# initial.net
KiCad netlist of a schematic drawn in Altium Designer
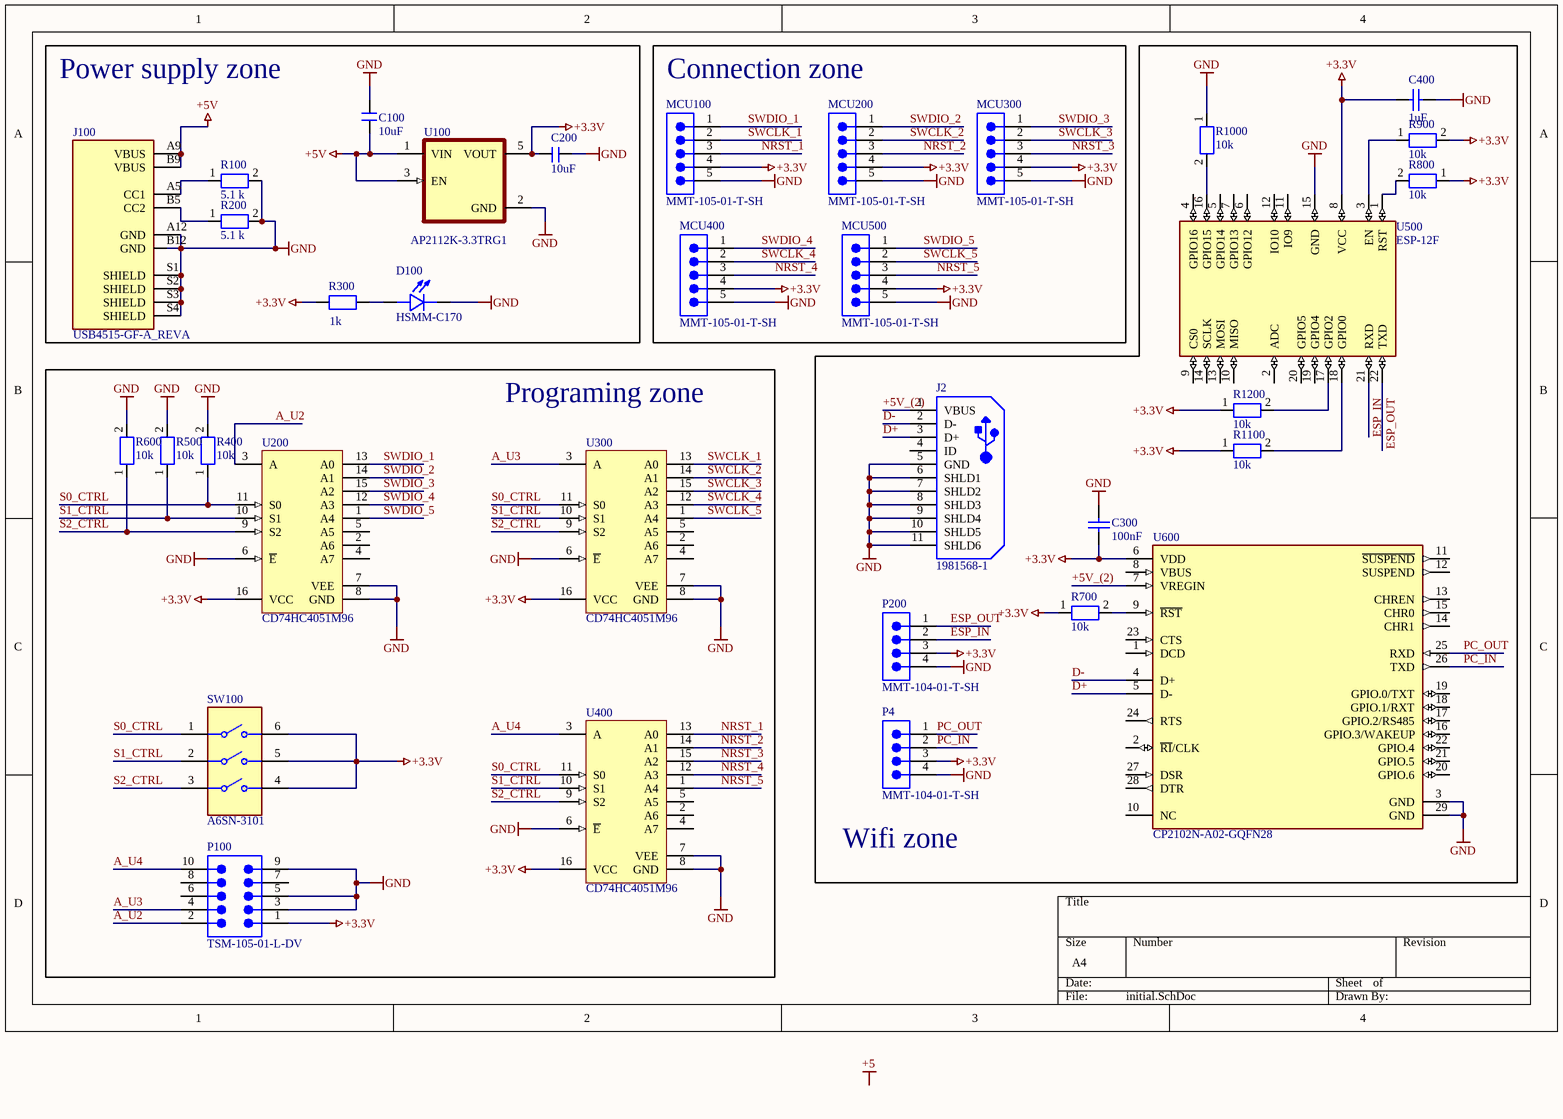
[diagram p0: initial.SchDoc]

(export (version "E")
  (design (tool "Eeschema 10.0.6"))
  (components
    (comp (ref "C100")
      (value "10uF")
      (footprint "CAPC2012X145N")
      (description "10 ÂµF Â±10% 25V Ceramic Capacitor X5R 0805 (2012 Metric)")
      (fields (field (name "MF") "Samsung") (field (name "MP") "CL21A106KAYNNNE"))
      (libsource (lib "CL21A106KAYNNNE") (part "CL21A106KAYNNNE"))
    )
    (comp (ref "C200")
      (value "10uF")
      (footprint "CAPC2012X145N")
      (description "10 ÂµF Â±10% 25V Ceramic Capacitor X5R 0805 (2012 Metric)")
      (fields (field (name "MF") "Samsung") (field (name "MP") "CL21A106KAYNNNE"))
      (libsource (lib "CL21A106KAYNNNE") (part "CL21A106KAYNNNE"))
    )
    (comp (ref "C300")
      (value "100nF")
      (footprint "CAPC2013X135X50LL15T20")
      (fields (field (name "MANUFACTURER") "Vitramon") (field (name "PART NUMBER") "VJ0805Y104KXJCW1BC"))
      (libsource (lib "Altium Content Vault") (part "CAP"))
    )
    (comp (ref "C400")
      (value "1uF")
      (footprint "CAPC2013X140X50NL20T25")
      (fields
        (field (name "PART NUMBER") "0805YD105MAT2A")
        (field (name "MANUFACTURER") "AVX Interconnect / Elco")
      )
      (libsource (lib "Altium Content Vault") (part "CAP"))
    )
    (comp (ref "D100")
      (value "HSMM-C170")
      (footprint "LED_HSMM-C170")
      (libsource (lib "HSMM-C170") (part "HSMM-C170"))
    )
    (comp (ref "J2")
      (value "1981568-1")
      (footprint "TECO-1981568-5_V")
      (description "Micro USB Receptacle Standard Type B Assy, 5-Pin SMD, RoHS, Tape and Reel")
      (fields (field (name "MANUFACTURER") "TE Connectivity"))
      (libsource (lib "Altium Content Vault") (part "USB-5-6SHLD"))
    )
    (comp (ref "J100")
      (value "USB4515-GF-A_REVA")
      (footprint "GCT_USB4515-GF-A_REVA")
      (description "Type C USB Charging Connector")
      (fields
        (field (name "MF") "Global Connector Technology")
        (field (name "DIGI-KEY_PART_NUMBER") "2073-USB4515-GF-ATR-ND")
      )
      (libsource (lib "USB4515-GF-A_REVA") (part "USB4515-GF-A_REVA"))
    )
    (comp (ref "MCU100")
      (value "MMT-105-01-T-SH")
      (footprint "SMTC-MMT-105-01-X-SH")
      (description "Horizontal Surface Mount Header, -55 to 105 degC, 2 mm Pitch, 5-Pin, Male, RoHS")
      (fields (field (name "MANUFACTURER") "Samtec"))
      (libsource (lib "Altium Content Vault") (part "SMTC-MMT-105-01-X-SH"))
    )
    (comp (ref "MCU200")
      (value "MMT-105-01-T-SH")
      (footprint "SMTC-MMT-105-01-X-SH")
      (description "Horizontal Surface Mount Header, -55 to 105 degC, 2 mm Pitch, 5-Pin, Male, RoHS")
      (fields (field (name "MANUFACTURER") "Samtec"))
      (libsource (lib "Altium Content Vault") (part "SMTC-MMT-105-01-X-SH"))
    )
    (comp (ref "MCU300")
      (value "MMT-105-01-T-SH")
      (footprint "SMTC-MMT-105-01-X-SH")
      (description "Horizontal Surface Mount Header, -55 to 105 degC, 2 mm Pitch, 5-Pin, Male, RoHS")
      (fields (field (name "MANUFACTURER") "Samtec"))
      (libsource (lib "Altium Content Vault") (part "SMTC-MMT-105-01-X-SH"))
    )
    (comp (ref "MCU400")
      (value "MMT-105-01-T-SH")
      (footprint "SMTC-MMT-105-01-X-SH")
      (description "Horizontal Surface Mount Header, -55 to 105 degC, 2 mm Pitch, 5-Pin, Male, RoHS")
      (fields (field (name "MANUFACTURER") "Samtec"))
      (libsource (lib "Altium Content Vault") (part "SMTC-MMT-105-01-X-SH"))
    )
    (comp (ref "MCU500")
      (value "MMT-105-01-T-SH")
      (footprint "SMTC-MMT-105-01-X-SH")
      (description "Horizontal Surface Mount Header, -55 to 105 degC, 2 mm Pitch, 5-Pin, Male, RoHS")
      (fields (field (name "MANUFACTURER") "Samtec"))
      (libsource (lib "Altium Content Vault") (part "SMTC-MMT-105-01-X-SH"))
    )
    (comp (ref "P4")
      (value "MMT-104-01-T-SH")
      (footprint "SMTC-MMT-104-01-X-SH")
      (description "Horizontal Surface Mount Header, -55 to 105 degC, 2 mm Pitch, 4-Pin, Male, RoHS")
      (fields (field (name "MANUFACTURER") "Samtec"))
      (libsource (lib "Altium Content Vault") (part "SMTC-MMT-104-X-X-SH"))
    )
    (comp (ref "P100")
      (value "TSM-105-01-L-DV")
      (footprint "SMTC-TSM-105-01-X-DV")
      (fields (field (name "MANUFACTURER") "Samtec"))
      (libsource (lib "Altium Content Vault") (part "SMTC-TSM-105-01-X-X"))
    )
    (comp (ref "P200")
      (value "MMT-104-01-T-SH")
      (footprint "SMTC-MMT-104-01-X-SH")
      (description "Horizontal Surface Mount Header, -55 to 105 degC, 2 mm Pitch, 4-Pin, Male, RoHS")
      (fields (field (name "MANUFACTURER") "Samtec"))
      (libsource (lib "Altium Content Vault") (part "SMTC-MMT-104-X-X-SH"))
    )
    (comp (ref "R100")
      (value "5.1 k")
      (footprint "FP-KTR10-IPC_B")
      (description "Res Thick Film 0805 5.1kΩ 1% 0.125W ±100ppm/°C Automotive Paper T/R")
      (fields (field (name "TOLERANCE") "1%"))
      (libsource (lib "Rez5.1") (part "CMP-08839-031572-1"))
    )
    (comp (ref "R200")
      (value "5.1 k")
      (footprint "FP-KTR10-IPC_B")
      (description "Res Thick Film 0805 5.1kΩ 1% 0.125W ±100ppm/°C Automotive Paper T/R")
      (fields (field (name "TOLERANCE") "1%"))
      (libsource (lib "Rez5.1") (part "CMP-08839-031572-1"))
    )
    (comp (ref "R300")
      (value "1k")
      (footprint "RESC2012X60N")
      (fields (field (name "MP") "CRS0805-JX-102ELF") (field (name "MF") "Bourns"))
      (libsource (lib "1Kohm_rez") (part "CRS0805-JX-102ELF"))
    )
    (comp (ref "R400")
      (value "10k")
      (footprint "FP-CRGP0805-IPC_A")
      (description "CRGP 0805 10K 1%")
      (fields (field (name "MANUFACTURER PART NUMBER") "CRGP0805F10K") (field (name "MANUFACTURER") "TE"))
      (libsource (lib "Rez_5.1K_0805") (part "CMP-03211-006861-1"))
    )
    (comp (ref "R500")
      (value "10k")
      (footprint "FP-CRGP0805-IPC_A")
      (description "CRGP 0805 10K 1%")
      (fields (field (name "MANUFACTURER PART NUMBER") "CRGP0805F10K") (field (name "MANUFACTURER") "TE"))
      (libsource (lib "Rez_5.1K_0805") (part "CMP-03211-006861-1"))
    )
    (comp (ref "R600")
      (value "10k")
      (footprint "FP-CRGP0805-IPC_A")
      (description "CRGP 0805 10K 1%")
      (fields (field (name "MANUFACTURER PART NUMBER") "CRGP0805F10K") (field (name "MANUFACTURER") "TE"))
      (libsource (lib "Rez_5.1K_0805") (part "CMP-03211-006861-1"))
    )
    (comp (ref "R700")
      (value "10k")
      (footprint "FP-CRGP0805-IPC_A")
      (description "CRGP 0805 10K 1%")
      (fields (field (name "MANUFACTURER PART NUMBER") "CRGP0805F10K") (field (name "MANUFACTURER") "TE"))
      (libsource (lib "Rez_5.1K_0805") (part "CMP-03211-006861-1"))
    )
    (comp (ref "R800")
      (value "10k")
      (footprint "FP-CRGP0805-IPC_A")
      (description "CRGP 0805 10K 1%")
      (fields (field (name "MANUFACTURER PART NUMBER") "CRGP0805F10K") (field (name "MANUFACTURER") "TE"))
      (libsource (lib "Rez_5.1K_0805") (part "CMP-03211-006861-1"))
    )
    (comp (ref "R900")
      (value "10k")
      (footprint "FP-CRGP0805-IPC_A")
      (description "CRGP 0805 10K 1%")
      (fields (field (name "MANUFACTURER PART NUMBER") "CRGP0805F10K") (field (name "MANUFACTURER") "TE"))
      (libsource (lib "Rez_5.1K_0805") (part "CMP-03211-006861-1"))
    )
    (comp (ref "R1000")
      (value "10k")
      (footprint "FP-CRGP0805-IPC_A")
      (description "CRGP 0805 10K 1%")
      (fields (field (name "MANUFACTURER PART NUMBER") "CRGP0805F10K") (field (name "MANUFACTURER") "TE"))
      (libsource (lib "Rez_5.1K_0805") (part "CMP-03211-006861-1"))
    )
    (comp (ref "R1100")
      (value "10k")
      (footprint "FP-CRGP0805-IPC_A")
      (description "CRGP 0805 10K 1%")
      (fields (field (name "MANUFACTURER PART NUMBER") "CRGP0805F10K") (field (name "MANUFACTURER") "TE"))
      (libsource (lib "Rez_5.1K_0805") (part "CMP-03211-006861-1"))
    )
    (comp (ref "R1200")
      (value "10k")
      (footprint "FP-CRGP0805-IPC_A")
      (description "CRGP 0805 10K 1%")
      (fields (field (name "MANUFACTURER PART NUMBER") "CRGP0805F10K") (field (name "MANUFACTURER") "TE"))
      (libsource (lib "Rez_5.1K_0805") (part "CMP-03211-006861-1"))
    )
    (comp (ref "SW100")
      (value "A6SN-3101")
      (footprint "FP-A6SN-3101-MFG")
      (description "SWITCH SLIDE DIP SPST 25MA 24V")
      (fields
        (field (name "MANUFACTURER") "Omron Electronics Inc-EMC Div")
        (field (name "OCTOPART") "https://octopart.com/a6sn-3101-omron-55396000")
      )
      (libsource (lib "Altium Content Vault") (part "c5ed29025a0a80be921a75429a93ff4"))
    )
    (comp (ref "U100")
      (value "AP2112K-3.3TRG1")
      (footprint "SOT95P285X140-5N")
      (description "Linear Voltage Regulator IC Positive Fixed 1 Output 600mA SOT-25")
      (fields (field (name "MF") "Diodes Inc."))
      (libsource (lib "AP2112K-3.3TRG1") (part "AP2112K-3.3TRG1"))
    )
    (comp (ref "U200")
      (value "CD74HC4051M96")
      (footprint "D0016A_M")
      (description "High Speed CMOS 8-Channel Analog Multiplexer/Demultiplexer, D0016A, LARGE T&R")
      (fields
        (field (name "GENERIC PART NUMBER") "CD74HC4051")
        (field (name "MANUFACTURER") "Texas Instruments")
      )
      (libsource (lib "Altium Content Vault") (part "TI-CD74HCX4051-16"))
    )
    (comp (ref "U300")
      (value "CD74HC4051M96")
      (footprint "D0016A_M")
      (description "High Speed CMOS 8-Channel Analog Multiplexer/Demultiplexer, D0016A, LARGE T&R")
      (fields
        (field (name "GENERIC PART NUMBER") "CD74HC4051")
        (field (name "MANUFACTURER") "Texas Instruments")
      )
      (libsource (lib "Altium Content Vault") (part "TI-CD74HCX4051-16"))
    )
    (comp (ref "U400")
      (value "CD74HC4051M96")
      (footprint "D0016A_M")
      (description "High Speed CMOS 8-Channel Analog Multiplexer/Demultiplexer, D0016A, LARGE T&R")
      (fields
        (field (name "GENERIC PART NUMBER") "CD74HC4051")
        (field (name "MANUFACTURER") "Texas Instruments")
      )
      (libsource (lib "Altium Content Vault") (part "TI-CD74HCX4051-16"))
    )
    (comp (ref "U500")
      (value "ESP-12F")
      (footprint "ESP-12F")
      (description "WiFi Module")
      (fields (field (name "MF") "AI-Thinker"))
      (libsource (lib "ESP-12F") (part "ESP-12F"))
    )
    (comp (ref "U600")
      (value "CP2102N-A02-GQFN28")
      (footprint "FP-CP2102N-A02-GQFN28-MFG")
      (description "IC USB TO UART BRIDGE QFN28")
      (libsource (lib "Altium Content Vault") (part "f8fb43f618a03b32512863a7a8093b6"))
    )
  )
  (nets
    (net (code "1") (name "+3.3V") (class "Default")
      (node (ref "C200") (pin "1") (pinfunction "1_1") (pintype "passive"))
      (node (ref "C300") (pin "1") (pinfunction "1_1") (pintype "passive"))
      (node (ref "C400") (pin "2") (pinfunction "2_2") (pintype "passive"))
      (node (ref "MCU100") (pin "4") (pinfunction "4_4") (pintype "passive"))
      (node (ref "MCU200") (pin "4") (pinfunction "4_4") (pintype "passive"))
      (node (ref "MCU300") (pin "4") (pinfunction "4_4") (pintype "passive"))
      (node (ref "MCU400") (pin "4") (pinfunction "4_4") (pintype "passive"))
      (node (ref "MCU500") (pin "4") (pinfunction "4_4") (pintype "passive"))
      (node (ref "P100") (pin "1") (pinfunction "1_1") (pintype "passive"))
      (node (ref "P200") (pin "3") (pinfunction "3_3") (pintype "passive"))
      (node (ref "P4") (pin "3") (pinfunction "3_3") (pintype "passive"))
      (node (ref "R1100") (pin "1") (pinfunction "1_1") (pintype "passive"))
      (node (ref "R1200") (pin "1") (pinfunction "1_1") (pintype "passive"))
      (node (ref "R300") (pin "1") (pinfunction "1_1") (pintype "passive"))
      (node (ref "R700") (pin "1") (pinfunction "1_1") (pintype "passive"))
      (node (ref "R800") (pin "1") (pinfunction "1_1") (pintype "passive"))
      (node (ref "R900") (pin "2") (pinfunction "2_2") (pintype "passive"))
      (node (ref "SW100") (pin "4") (pinfunction "4_4") (pintype "passive"))
      (node (ref "SW100") (pin "5") (pinfunction "5_5") (pintype "passive"))
      (node (ref "SW100") (pin "6") (pinfunction "6_6") (pintype "passive"))
      (node (ref "U100") (pin "5") (pinfunction "VOUT_5") (pintype "power_in"))
      (node (ref "U200") (pin "16") (pinfunction "VCC_16") (pintype "power_in"))
      (node (ref "U300") (pin "16") (pinfunction "VCC_16") (pintype "power_in"))
      (node (ref "U400") (pin "16") (pinfunction "VCC_16") (pintype "power_in"))
      (node (ref "U500") (pin "8") (pinfunction "VCC_8") (pintype "bidirectional"))
      (node (ref "U600") (pin "6") (pinfunction "VDD_6") (pintype "power_in"))
    )
    (net (code "3") (name "+5V") (class "Default")
      (node (ref "C100") (pin "2") (pinfunction "2_2") (pintype "passive"))
      (node (ref "J100") (pin "A9") (pinfunction "VBUS_A9") (pintype "power_in"))
      (node (ref "J100") (pin "B9") (pinfunction "VBUS_B9") (pintype "power_in"))
      (node (ref "U100") (pin "1") (pinfunction "VIN_1") (pintype "power_in"))
      (node (ref "U100") (pin "3") (pinfunction "EN_3") (pintype "input"))
    )
    (net (code "4") (name "/+5V_(2)") (class "Default")
      (node (ref "J2") (pin "1") (pinfunction "VBUS_1") (pintype "passive"))
      (node (ref "U600") (pin "7") (pinfunction "VREGIN_7") (pintype "input"))
    )
    (net (code "5") (name "/A_U2") (class "Default")
      (node (ref "P100") (pin "2") (pinfunction "2_2") (pintype "passive"))
      (node (ref "U200") (pin "3") (pinfunction "A_3") (pintype "passive"))
    )
    (net (code "6") (name "/A_U3") (class "Default")
      (node (ref "P100") (pin "4") (pinfunction "4_4") (pintype "passive"))
      (node (ref "U300") (pin "3") (pinfunction "A_3") (pintype "passive"))
    )
    (net (code "7") (name "/A_U4") (class "Default")
      (node (ref "P100") (pin "10") (pinfunction "10_10") (pintype "passive"))
      (node (ref "U400") (pin "3") (pinfunction "A_3") (pintype "passive"))
    )
    (net (code "8") (name "/D+") (class "Default")
      (node (ref "J2") (pin "3") (pinfunction "D+_3") (pintype "passive"))
      (node (ref "U600") (pin "5") (pinfunction "D-_5") (pintype "passive"))
    )
    (net (code "9") (name "/D-") (class "Default")
      (node (ref "J2") (pin "2") (pinfunction "D-_2") (pintype "passive"))
      (node (ref "U600") (pin "4") (pinfunction "D+_4") (pintype "passive"))
    )
    (net (code "10") (name "/ESP_IN") (class "Default")
      (node (ref "P200") (pin "2") (pinfunction "2_2") (pintype "passive"))
      (node (ref "U500") (pin "21") (pinfunction "RXD_21") (pintype "bidirectional"))
    )
    (net (code "11") (name "/ESP_OUT") (class "Default")
      (node (ref "P200") (pin "1") (pinfunction "1_1") (pintype "passive"))
      (node (ref "U500") (pin "22") (pinfunction "TXD_22") (pintype "bidirectional"))
    )
    (net (code "12") (name "/NRST_1") (class "Default")
      (node (ref "MCU100") (pin "3") (pinfunction "3_3") (pintype "passive"))
      (node (ref "U400") (pin "13") (pinfunction "A0_13") (pintype "passive"))
    )
    (net (code "13") (name "/NRST_2") (class "Default")
      (node (ref "MCU200") (pin "3") (pinfunction "3_3") (pintype "passive"))
      (node (ref "U400") (pin "14") (pinfunction "A1_14") (pintype "passive"))
    )
    (net (code "14") (name "/NRST_3") (class "Default")
      (node (ref "MCU300") (pin "3") (pinfunction "3_3") (pintype "passive"))
      (node (ref "U400") (pin "15") (pinfunction "A2_15") (pintype "passive"))
    )
    (net (code "15") (name "/NRST_4") (class "Default")
      (node (ref "MCU400") (pin "3") (pinfunction "3_3") (pintype "passive"))
      (node (ref "U400") (pin "12") (pinfunction "A3_12") (pintype "passive"))
    )
    (net (code "16") (name "/NRST_5") (class "Default")
      (node (ref "MCU500") (pin "3") (pinfunction "3_3") (pintype "passive"))
      (node (ref "U400") (pin "1") (pinfunction "A4_1") (pintype "passive"))
    )
    (net (code "17") (name "/PC_IN") (class "Default")
      (node (ref "P4") (pin "2") (pinfunction "2_2") (pintype "passive"))
      (node (ref "U600") (pin "26") (pinfunction "TXD_26") (pintype "output"))
    )
    (net (code "18") (name "/PC_OUT") (class "Default")
      (node (ref "P4") (pin "1") (pinfunction "1_1") (pintype "passive"))
      (node (ref "U600") (pin "25") (pinfunction "RXD_25") (pintype "input"))
    )
    (net (code "19") (name "/S0_CTRL") (class "Default")
      (node (ref "R400") (pin "1") (pinfunction "1_1") (pintype "passive"))
      (node (ref "SW100") (pin "1") (pinfunction "1_1") (pintype "passive"))
      (node (ref "U200") (pin "11") (pinfunction "S0_11") (pintype "input"))
      (node (ref "U300") (pin "11") (pinfunction "S0_11") (pintype "input"))
      (node (ref "U400") (pin "11") (pinfunction "S0_11") (pintype "input"))
    )
    (net (code "20") (name "/S1_CTRL") (class "Default")
      (node (ref "R500") (pin "1") (pinfunction "1_1") (pintype "passive"))
      (node (ref "SW100") (pin "2") (pinfunction "2_2") (pintype "passive"))
      (node (ref "U200") (pin "10") (pinfunction "S1_10") (pintype "input"))
      (node (ref "U300") (pin "10") (pinfunction "S1_10") (pintype "input"))
      (node (ref "U400") (pin "10") (pinfunction "S1_10") (pintype "input"))
    )
    (net (code "21") (name "/S2_CTRL") (class "Default")
      (node (ref "R600") (pin "1") (pinfunction "1_1") (pintype "passive"))
      (node (ref "SW100") (pin "3") (pinfunction "3_3") (pintype "passive"))
      (node (ref "U200") (pin "9") (pinfunction "S2_9") (pintype "input"))
      (node (ref "U300") (pin "9") (pinfunction "S2_9") (pintype "input"))
      (node (ref "U400") (pin "9") (pinfunction "S2_9") (pintype "input"))
    )
    (net (code "22") (name "/SWCLK_1") (class "Default")
      (node (ref "MCU100") (pin "2") (pinfunction "2_2") (pintype "passive"))
      (node (ref "U300") (pin "13") (pinfunction "A0_13") (pintype "passive"))
    )
    (net (code "23") (name "/SWCLK_2") (class "Default")
      (node (ref "MCU200") (pin "2") (pinfunction "2_2") (pintype "passive"))
      (node (ref "U300") (pin "14") (pinfunction "A1_14") (pintype "passive"))
    )
    (net (code "24") (name "/SWCLK_3") (class "Default")
      (node (ref "MCU300") (pin "2") (pinfunction "2_2") (pintype "passive"))
      (node (ref "U300") (pin "15") (pinfunction "A2_15") (pintype "passive"))
    )
    (net (code "25") (name "/SWCLK_4") (class "Default")
      (node (ref "MCU400") (pin "2") (pinfunction "2_2") (pintype "passive"))
      (node (ref "U300") (pin "12") (pinfunction "A3_12") (pintype "passive"))
    )
    (net (code "26") (name "/SWCLK_5") (class "Default")
      (node (ref "MCU500") (pin "2") (pinfunction "2_2") (pintype "passive"))
      (node (ref "U300") (pin "1") (pinfunction "A4_1") (pintype "passive"))
    )
    (net (code "27") (name "/SWDIO_1") (class "Default")
      (node (ref "MCU100") (pin "1") (pinfunction "1_1") (pintype "passive"))
      (node (ref "U200") (pin "13") (pinfunction "A0_13") (pintype "passive"))
    )
    (net (code "28") (name "/SWDIO_2") (class "Default")
      (node (ref "MCU200") (pin "1") (pinfunction "1_1") (pintype "passive"))
      (node (ref "U200") (pin "14") (pinfunction "A1_14") (pintype "passive"))
    )
    (net (code "29") (name "/SWDIO_3") (class "Default")
      (node (ref "MCU300") (pin "1") (pinfunction "1_1") (pintype "passive"))
      (node (ref "U200") (pin "15") (pinfunction "A2_15") (pintype "passive"))
    )
    (net (code "30") (name "/SWDIO_4") (class "Default")
      (node (ref "MCU400") (pin "1") (pinfunction "1_1") (pintype "passive"))
      (node (ref "U200") (pin "12") (pinfunction "A3_12") (pintype "passive"))
    )
    (net (code "31") (name "/SWDIO_5") (class "Default")
      (node (ref "MCU500") (pin "1") (pinfunction "1_1") (pintype "passive"))
      (node (ref "U200") (pin "1") (pinfunction "A4_1") (pintype "passive"))
    )
    (net (code "32") (name "GND") (class "Default")
      (node (ref "C100") (pin "1") (pinfunction "1_1") (pintype "passive"))
      (node (ref "C200") (pin "2") (pinfunction "2_2") (pintype "passive"))
      (node (ref "C300") (pin "2") (pinfunction "2_2") (pintype "passive"))
      (node (ref "C400") (pin "1") (pinfunction "1_1") (pintype "passive"))
      (node (ref "D100") (pin "C") (pinfunction "C_C") (pintype "passive"))
      (node (ref "J100") (pin "A12") (pinfunction "GND_A12") (pintype "power_in"))
      (node (ref "J100") (pin "B12") (pinfunction "GND_B12") (pintype "power_in"))
      (node (ref "J100") (pin "S1") (pinfunction "SHIELD_S1") (pintype "power_in"))
      (node (ref "J100") (pin "S2") (pinfunction "SHIELD_S2") (pintype "power_in"))
      (node (ref "J100") (pin "S3") (pinfunction "SHIELD_S3") (pintype "power_in"))
      (node (ref "J100") (pin "S4") (pinfunction "SHIELD_S4") (pintype "power_in"))
      (node (ref "J2") (pin "10") (pinfunction "SHLD5_10") (pintype "passive"))
      (node (ref "J2") (pin "11") (pinfunction "SHLD6_11") (pintype "passive"))
      (node (ref "J2") (pin "5") (pinfunction "GND_5") (pintype "passive"))
      (node (ref "J2") (pin "6") (pinfunction "SHLD1_6") (pintype "passive"))
      (node (ref "J2") (pin "7") (pinfunction "SHLD2_7") (pintype "passive"))
      (node (ref "J2") (pin "8") (pinfunction "SHLD3_8") (pintype "passive"))
      (node (ref "J2") (pin "9") (pinfunction "SHLD4_9") (pintype "passive"))
      (node (ref "MCU100") (pin "5") (pinfunction "5_5") (pintype "passive"))
      (node (ref "MCU200") (pin "5") (pinfunction "5_5") (pintype "passive"))
      (node (ref "MCU300") (pin "5") (pinfunction "5_5") (pintype "passive"))
      (node (ref "MCU400") (pin "5") (pinfunction "5_5") (pintype "passive"))
      (node (ref "MCU500") (pin "5") (pinfunction "5_5") (pintype "passive"))
      (node (ref "P100") (pin "3") (pinfunction "3_3") (pintype "passive"))
      (node (ref "P100") (pin "5") (pinfunction "5_5") (pintype "passive"))
      (node (ref "P100") (pin "9") (pinfunction "9_9") (pintype "passive"))
      (node (ref "P200") (pin "4") (pinfunction "4_4") (pintype "passive"))
      (node (ref "P4") (pin "4") (pinfunction "4_4") (pintype "passive"))
      (node (ref "R100") (pin "2") (pinfunction "2_2") (pintype "passive"))
      (node (ref "R1000") (pin "1") (pinfunction "1_1") (pintype "passive"))
      (node (ref "R200") (pin "2") (pinfunction "2_2") (pintype "passive"))
      (node (ref "R400") (pin "2") (pinfunction "2_2") (pintype "passive"))
      (node (ref "R500") (pin "2") (pinfunction "2_2") (pintype "passive"))
      (node (ref "R600") (pin "2") (pinfunction "2_2") (pintype "passive"))
      (node (ref "U100") (pin "2") (pinfunction "GND_2") (pintype "power_in"))
      (node (ref "U200") (pin "6") (pinfunction "~{E}_6") (pintype "input"))
      (node (ref "U200") (pin "7") (pinfunction "VEE_7") (pintype "power_in"))
      (node (ref "U200") (pin "8") (pinfunction "GND_8") (pintype "power_in"))
      (node (ref "U300") (pin "6") (pinfunction "~{E}_6") (pintype "input"))
      (node (ref "U300") (pin "7") (pinfunction "VEE_7") (pintype "power_in"))
      (node (ref "U300") (pin "8") (pinfunction "GND_8") (pintype "power_in"))
      (node (ref "U400") (pin "6") (pinfunction "~{E}_6") (pintype "input"))
      (node (ref "U400") (pin "7") (pinfunction "VEE_7") (pintype "power_in"))
      (node (ref "U400") (pin "8") (pinfunction "GND_8") (pintype "power_in"))
      (node (ref "U500") (pin "15") (pinfunction "GND_15") (pintype "bidirectional"))
      (node (ref "U600") (pin "29") (pinfunction "GND_29") (pintype "power_in"))
      (node (ref "U600") (pin "3") (pinfunction "GND_3") (pintype "power_in"))
    )
    (net (code "33") (name "Net-(D100-PadA)") (class "Default")
      (node (ref "D100") (pin "A") (pinfunction "A_A") (pintype "passive"))
      (node (ref "R300") (pin "2") (pinfunction "2_2") (pintype "passive"))
    )
    (net (code "34") (name "Net-(J100-CC1)") (class "Default")
      (node (ref "J100") (pin "A5") (pinfunction "CC1_A5") (pintype "passive"))
      (node (ref "R100") (pin "1") (pinfunction "1_1") (pintype "passive"))
    )
    (net (code "35") (name "Net-(J100-CC2)") (class "Default")
      (node (ref "J100") (pin "B5") (pinfunction "CC2_B5") (pintype "passive"))
      (node (ref "R200") (pin "1") (pinfunction "1_1") (pintype "passive"))
    )
    (net (code "36") (name "Net-(U500-EN)") (class "Default")
      (node (ref "R900") (pin "1") (pinfunction "1_1") (pintype "passive"))
      (node (ref "U500") (pin "3") (pinfunction "EN_3") (pintype "bidirectional"))
    )
    (net (code "37") (name "Net-(U500-GPIO0)") (class "Default")
      (node (ref "R1100") (pin "2") (pinfunction "2_2") (pintype "passive"))
      (node (ref "U500") (pin "18") (pinfunction "GPIO0_18") (pintype "bidirectional"))
    )
    (net (code "38") (name "Net-(U500-GPIO2)") (class "Default")
      (node (ref "R1200") (pin "2") (pinfunction "2_2") (pintype "passive"))
      (node (ref "U500") (pin "17") (pinfunction "GPIO2_17") (pintype "bidirectional"))
    )
    (net (code "39") (name "Net-(U500-GPIO15)") (class "Default")
      (node (ref "R1000") (pin "2") (pinfunction "2_2") (pintype "passive"))
      (node (ref "U500") (pin "16") (pinfunction "GPIO15_16") (pintype "bidirectional"))
    )
    (net (code "40") (name "Net-(U500-RST)") (class "Default")
      (node (ref "R800") (pin "2") (pinfunction "2_2") (pintype "passive"))
      (node (ref "U500") (pin "1") (pinfunction "RST_1") (pintype "bidirectional"))
    )
    (net (code "41") (name "Net-(U600-~{RST})") (class "Default")
      (node (ref "R700") (pin "2") (pinfunction "2_2") (pintype "passive"))
      (node (ref "U600") (pin "9") (pinfunction "~{RST}_9") (pintype "input"))
    )
    (net (code "42") (name "unconnected-(J2-ID-Pad4)") (class "Default")
      (node (ref "J2") (pin "4") (pinfunction "ID_4") (pintype "passive"))
    )
    (net (code "43") (name "unconnected-(P100-Pad6)") (class "Default")
      (node (ref "P100") (pin "6") (pinfunction "6_6") (pintype "passive"))
    )
    (net (code "44") (name "unconnected-(P100-Pad7)") (class "Default")
      (node (ref "P100") (pin "7") (pinfunction "7_7") (pintype "passive"))
    )
    (net (code "45") (name "unconnected-(P100-Pad8)") (class "Default")
      (node (ref "P100") (pin "8") (pinfunction "8_8") (pintype "passive"))
    )
    (net (code "46") (name "unconnected-(U200-A5-Pad5)") (class "Default")
      (node (ref "U200") (pin "5") (pinfunction "A5_5") (pintype "passive"))
    )
    (net (code "47") (name "unconnected-(U200-A6-Pad2)") (class "Default")
      (node (ref "U200") (pin "2") (pinfunction "A6_2") (pintype "passive"))
    )
    (net (code "48") (name "unconnected-(U200-A7-Pad4)") (class "Default")
      (node (ref "U200") (pin "4") (pinfunction "A7_4") (pintype "passive"))
    )
    (net (code "49") (name "unconnected-(U300-A5-Pad5)") (class "Default")
      (node (ref "U300") (pin "5") (pinfunction "A5_5") (pintype "passive"))
    )
    (net (code "50") (name "unconnected-(U300-A6-Pad2)") (class "Default")
      (node (ref "U300") (pin "2") (pinfunction "A6_2") (pintype "passive"))
    )
    (net (code "51") (name "unconnected-(U300-A7-Pad4)") (class "Default")
      (node (ref "U300") (pin "4") (pinfunction "A7_4") (pintype "passive"))
    )
    (net (code "52") (name "unconnected-(U400-A5-Pad5)") (class "Default")
      (node (ref "U400") (pin "5") (pinfunction "A5_5") (pintype "passive"))
    )
    (net (code "53") (name "unconnected-(U400-A6-Pad2)") (class "Default")
      (node (ref "U400") (pin "2") (pinfunction "A6_2") (pintype "passive"))
    )
    (net (code "54") (name "unconnected-(U400-A7-Pad4)") (class "Default")
      (node (ref "U400") (pin "4") (pinfunction "A7_4") (pintype "passive"))
    )
    (net (code "55") (name "unconnected-(U500-ADC-Pad2)") (class "Default")
      (node (ref "U500") (pin "2") (pinfunction "ADC_2") (pintype "bidirectional"))
    )
    (net (code "56") (name "unconnected-(U500-CS0-Pad9)") (class "Default")
      (node (ref "U500") (pin "9") (pinfunction "CS0_9") (pintype "bidirectional"))
    )
    (net (code "57") (name "unconnected-(U500-GPIO4-Pad19)") (class "Default")
      (node (ref "U500") (pin "19") (pinfunction "GPIO4_19") (pintype "bidirectional"))
    )
    (net (code "58") (name "unconnected-(U500-GPIO5-Pad20)") (class "Default")
      (node (ref "U500") (pin "20") (pinfunction "GPIO5_20") (pintype "bidirectional"))
    )
    (net (code "59") (name "unconnected-(U500-GPIO12-Pad6)") (class "Default")
      (node (ref "U500") (pin "6") (pinfunction "GPIO12_6") (pintype "bidirectional"))
    )
    (net (code "60") (name "unconnected-(U500-GPIO13-Pad7)") (class "Default")
      (node (ref "U500") (pin "7") (pinfunction "GPIO13_7") (pintype "bidirectional"))
    )
    (net (code "61") (name "unconnected-(U500-GPIO14-Pad5)") (class "Default")
      (node (ref "U500") (pin "5") (pinfunction "GPIO14_5") (pintype "bidirectional"))
    )
    (net (code "62") (name "unconnected-(U500-GPIO16-Pad4)") (class "Default")
      (node (ref "U500") (pin "4") (pinfunction "GPIO16_4") (pintype "bidirectional"))
    )
    (net (code "63") (name "unconnected-(U500-IO9-Pad11)") (class "Default")
      (node (ref "U500") (pin "11") (pinfunction "IO9_11") (pintype "bidirectional"))
    )
    (net (code "64") (name "unconnected-(U500-IO10-Pad12)") (class "Default")
      (node (ref "U500") (pin "12") (pinfunction "IO10_12") (pintype "bidirectional"))
    )
    (net (code "65") (name "unconnected-(U500-MISO-Pad10)") (class "Default")
      (node (ref "U500") (pin "10") (pinfunction "MISO_10") (pintype "bidirectional"))
    )
    (net (code "66") (name "unconnected-(U500-MOSI-Pad13)") (class "Default")
      (node (ref "U500") (pin "13") (pinfunction "MOSI_13") (pintype "bidirectional"))
    )
    (net (code "67") (name "unconnected-(U500-SCLK-Pad14)") (class "Default")
      (node (ref "U500") (pin "14") (pinfunction "SCLK_14") (pintype "bidirectional"))
    )
    (net (code "68") (name "unconnected-(U600-CHR0-Pad15)") (class "Default")
      (node (ref "U600") (pin "15") (pinfunction "CHR0_15") (pintype "output"))
    )
    (net (code "69") (name "unconnected-(U600-CHR1-Pad14)") (class "Default")
      (node (ref "U600") (pin "14") (pinfunction "CHR1_14") (pintype "output"))
    )
    (net (code "70") (name "unconnected-(U600-CHREN-Pad13)") (class "Default")
      (node (ref "U600") (pin "13") (pinfunction "CHREN_13") (pintype "output"))
    )
    (net (code "71") (name "unconnected-(U600-CTS-Pad23)") (class "Default")
      (node (ref "U600") (pin "23") (pinfunction "CTS_23") (pintype "input"))
    )
    (net (code "72") (name "unconnected-(U600-DCD-Pad1)") (class "Default")
      (node (ref "U600") (pin "1") (pinfunction "DCD_1") (pintype "input"))
    )
    (net (code "73") (name "unconnected-(U600-DSR-Pad27)") (class "Default")
      (node (ref "U600") (pin "27") (pinfunction "DSR_27") (pintype "input"))
    )
    (net (code "74") (name "unconnected-(U600-DTR-Pad28)") (class "Default")
      (node (ref "U600") (pin "28") (pinfunction "DTR_28") (pintype "output"))
    )
    (net (code "75") (name "unconnected-(U600-GPIO.0{slash}TXT-Pad19)") (class "Default")
      (node (ref "U600") (pin "19") (pinfunction "GPIO.0/TXT_19") (pintype "bidirectional"))
    )
    (net (code "76") (name "unconnected-(U600-GPIO.1{slash}RXT-Pad18)") (class "Default")
      (node (ref "U600") (pin "18") (pinfunction "GPIO.1/RXT_18") (pintype "bidirectional"))
    )
    (net (code "77") (name "unconnected-(U600-GPIO.2{slash}RS485-Pad17)") (class "Default")
      (node (ref "U600") (pin "17") (pinfunction "GPIO.2/RS485_17") (pintype "bidirectional"))
    )
    (net (code "78") (name "unconnected-(U600-GPIO.3{slash}WAKEUP-Pad16)") (class "Default")
      (node (ref "U600") (pin "16") (pinfunction "GPIO.3/WAKEUP_16") (pintype "bidirectional"))
    )
    (net (code "79") (name "unconnected-(U600-GPIO.4-Pad22)") (class "Default")
      (node (ref "U600") (pin "22") (pinfunction "GPIO.4_22") (pintype "bidirectional"))
    )
    (net (code "80") (name "unconnected-(U600-GPIO.5-Pad21)") (class "Default")
      (node (ref "U600") (pin "21") (pinfunction "GPIO.5_21") (pintype "bidirectional"))
    )
    (net (code "81") (name "unconnected-(U600-GPIO.6-Pad20)") (class "Default")
      (node (ref "U600") (pin "20") (pinfunction "GPIO.6_20") (pintype "bidirectional"))
    )
    (net (code "82") (name "unconnected-(U600-NC-Pad10)") (class "Default")
      (node (ref "U600") (pin "10") (pinfunction "NC_10") (pintype "passive"))
    )
    (net (code "83") (name "unconnected-(U600-RTS-Pad24)") (class "Default")
      (node (ref "U600") (pin "24") (pinfunction "RTS_24") (pintype "output"))
    )
    (net (code "84") (name "unconnected-(U600-SUSPEND-Pad12)") (class "Default")
      (node (ref "U600") (pin "12") (pinfunction "SUSPEND_12") (pintype "output"))
    )
    (net (code "85") (name "unconnected-(U600-VBUS-Pad8)") (class "Default")
      (node (ref "U600") (pin "8") (pinfunction "VBUS_8") (pintype "input"))
    )
    (net (code "86") (name "unconnected-(U600-~{RI}{slash}CLK-Pad2)") (class "Default")
      (node (ref "U600") (pin "2") (pinfunction "~{RI}/CLK_2") (pintype "bidirectional"))
    )
    (net (code "87") (name "unconnected-(U600-~{SUSPEND}-Pad11)") (class "Default")
      (node (ref "U600") (pin "11") (pinfunction "~{SUSPEND}_11") (pintype "output"))
    )
  )
)
